# circuit.net
KiCad netlist of a schematic drawn in EAGLE
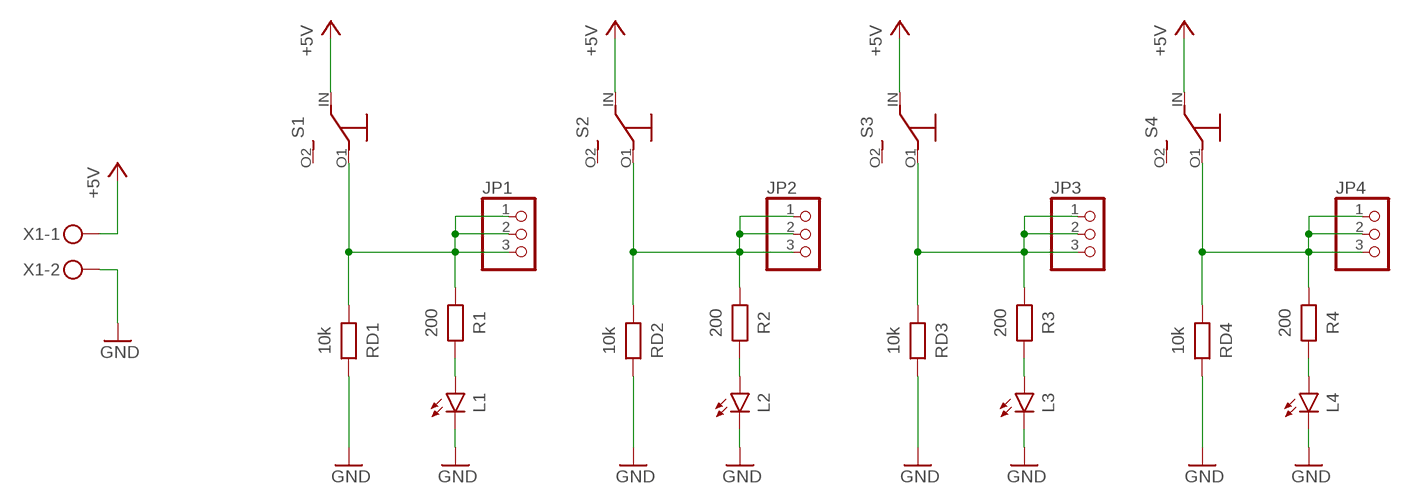
[diagram p0: schematic, sheet 1]

(export (version "E")
  (design (tool "Eeschema 10.0.6"))
  (components
    (comp (ref "JP1")
      (value "PINHD-1X3")
      (footprint "eagle-import:1X03")
      (libsource (lib "eagle-import") (part "PINHD-1X3"))
    )
    (comp (ref "JP2")
      (value "PINHD-1X3")
      (footprint "eagle-import:1X03")
      (libsource (lib "eagle-import") (part "PINHD-1X3"))
    )
    (comp (ref "JP3")
      (value "PINHD-1X3")
      (footprint "eagle-import:1X03")
      (libsource (lib "eagle-import") (part "PINHD-1X3"))
    )
    (comp (ref "JP4")
      (value "PINHD-1X3")
      (footprint "eagle-import:1X03")
      (libsource (lib "eagle-import") (part "PINHD-1X3"))
    )
    (comp (ref "L1")
      (value "LED-3MM")
      (footprint "eagle-import:LED_3MM")
      (libsource (lib "eagle-import") (part "LED-3MM"))
    )
    (comp (ref "L2")
      (value "LED-3MM")
      (footprint "eagle-import:LED_3MM")
      (libsource (lib "eagle-import") (part "LED-3MM"))
    )
    (comp (ref "L3")
      (value "LED-3MM")
      (footprint "eagle-import:LED_3MM")
      (libsource (lib "eagle-import") (part "LED-3MM"))
    )
    (comp (ref "L4")
      (value "LED-3MM")
      (footprint "eagle-import:LED_3MM")
      (libsource (lib "eagle-import") (part "LED-3MM"))
    )
    (comp (ref "R1")
      (value "200")
      (footprint "eagle-import:R_THT_4")
      (libsource (lib "eagle-import") (part "RESISTOR-10MM"))
    )
    (comp (ref "R2")
      (value "200")
      (footprint "eagle-import:R_THT_4")
      (libsource (lib "eagle-import") (part "RESISTOR-10MM"))
    )
    (comp (ref "R3")
      (value "200")
      (footprint "eagle-import:R_THT_4")
      (libsource (lib "eagle-import") (part "RESISTOR-10MM"))
    )
    (comp (ref "R4")
      (value "200")
      (footprint "eagle-import:R_THT_4")
      (libsource (lib "eagle-import") (part "RESISTOR-10MM"))
    )
    (comp (ref "RD1")
      (value "10k")
      (footprint "eagle-import:R_THT_4")
      (libsource (lib "eagle-import") (part "RESISTOR-10MM"))
    )
    (comp (ref "RD2")
      (value "10k")
      (footprint "eagle-import:R_THT_4")
      (libsource (lib "eagle-import") (part "RESISTOR-10MM"))
    )
    (comp (ref "RD3")
      (value "10k")
      (footprint "eagle-import:R_THT_4")
      (libsource (lib "eagle-import") (part "RESISTOR-10MM"))
    )
    (comp (ref "RD4")
      (value "10k")
      (footprint "eagle-import:R_THT_4")
      (libsource (lib "eagle-import") (part "RESISTOR-10MM"))
    )
    (comp (ref "S1")
      (value "SCHALTER_UM-KIPP")
      (footprint "eagle-import:SCHALTER_KIPP_UM")
      (libsource (lib "eagle-import") (part "SCHALTER_UM-KIPP"))
    )
    (comp (ref "S2")
      (value "SCHALTER_UM-KIPP")
      (footprint "eagle-import:SCHALTER_KIPP_UM")
      (libsource (lib "eagle-import") (part "SCHALTER_UM-KIPP"))
    )
    (comp (ref "S3")
      (value "SCHALTER_UM-KIPP")
      (footprint "eagle-import:SCHALTER_KIPP_UM")
      (libsource (lib "eagle-import") (part "SCHALTER_UM-KIPP"))
    )
    (comp (ref "S4")
      (value "SCHALTER_UM-KIPP")
      (footprint "eagle-import:SCHALTER_KIPP_UM")
      (libsource (lib "eagle-import") (part "SCHALTER_UM-KIPP"))
    )
    (comp (ref "X1")
      (value "STECKER_SPG_2")
      (footprint "eagle-import:STECKER_SPG_2")
      (libsource (lib "eagle-import") (part "STECKER_SPG_2"))
    )
  )
  (nets
    (net (code "1") (name "+5V") (class "Default")
      (node (ref "S1") (pin "IN") (pinfunction "IN_IN") (pintype "passive"))
      (node (ref "S2") (pin "IN") (pinfunction "IN_IN") (pintype "passive"))
      (node (ref "S3") (pin "IN") (pinfunction "IN_IN") (pintype "passive"))
      (node (ref "S4") (pin "IN") (pinfunction "IN_IN") (pintype "passive"))
      (node (ref "X1") (pin "1") (pinfunction "KL_1") (pintype "passive"))
    )
    (net (code "2") (name "GND") (class "Default")
      (node (ref "L1") (pin "K") (pinfunction "C_K") (pintype "passive"))
      (node (ref "L2") (pin "K") (pinfunction "C_K") (pintype "passive"))
      (node (ref "L3") (pin "K") (pinfunction "C_K") (pintype "passive"))
      (node (ref "L4") (pin "K") (pinfunction "C_K") (pintype "passive"))
      (node (ref "RD1") (pin "1") (pinfunction "P1_1") (pintype "passive"))
      (node (ref "RD2") (pin "1") (pinfunction "P1_1") (pintype "passive"))
      (node (ref "RD3") (pin "1") (pinfunction "P1_1") (pintype "passive"))
      (node (ref "RD4") (pin "1") (pinfunction "P1_1") (pintype "passive"))
      (node (ref "X1") (pin "2") (pinfunction "KL_2") (pintype "passive"))
    )
    (net (code "3") (name "Net-(R1-P1)") (class "Default")
      (node (ref "L1") (pin "A") (pinfunction "A_A") (pintype "passive"))
      (node (ref "R1") (pin "1") (pinfunction "P1_1") (pintype "passive"))
    )
    (net (code "4") (name "Net-(R1-P2)") (class "Default")
      (node (ref "JP1") (pin "1") (pinfunction "1_1") (pintype "passive"))
      (node (ref "JP1") (pin "2") (pinfunction "2_2") (pintype "passive"))
      (node (ref "JP1") (pin "3") (pinfunction "3_3") (pintype "passive"))
      (node (ref "R1") (pin "2") (pinfunction "P2_2") (pintype "passive"))
      (node (ref "RD1") (pin "2") (pinfunction "P2_2") (pintype "passive"))
      (node (ref "S1") (pin "O1") (pinfunction "O1_O1") (pintype "passive"))
    )
    (net (code "5") (name "Net-(R2-P1)") (class "Default")
      (node (ref "L2") (pin "A") (pinfunction "A_A") (pintype "passive"))
      (node (ref "R2") (pin "1") (pinfunction "P1_1") (pintype "passive"))
    )
    (net (code "6") (name "Net-(R2-P2)") (class "Default")
      (node (ref "JP2") (pin "1") (pinfunction "1_1") (pintype "passive"))
      (node (ref "JP2") (pin "2") (pinfunction "2_2") (pintype "passive"))
      (node (ref "JP2") (pin "3") (pinfunction "3_3") (pintype "passive"))
      (node (ref "R2") (pin "2") (pinfunction "P2_2") (pintype "passive"))
      (node (ref "RD2") (pin "2") (pinfunction "P2_2") (pintype "passive"))
      (node (ref "S2") (pin "O1") (pinfunction "O1_O1") (pintype "passive"))
    )
    (net (code "7") (name "Net-(R3-P1)") (class "Default")
      (node (ref "L3") (pin "A") (pinfunction "A_A") (pintype "passive"))
      (node (ref "R3") (pin "1") (pinfunction "P1_1") (pintype "passive"))
    )
    (net (code "8") (name "Net-(R3-P2)") (class "Default")
      (node (ref "JP3") (pin "1") (pinfunction "1_1") (pintype "passive"))
      (node (ref "JP3") (pin "2") (pinfunction "2_2") (pintype "passive"))
      (node (ref "JP3") (pin "3") (pinfunction "3_3") (pintype "passive"))
      (node (ref "R3") (pin "2") (pinfunction "P2_2") (pintype "passive"))
      (node (ref "RD3") (pin "2") (pinfunction "P2_2") (pintype "passive"))
      (node (ref "S3") (pin "O1") (pinfunction "O1_O1") (pintype "passive"))
    )
    (net (code "9") (name "Net-(R4-P1)") (class "Default")
      (node (ref "L4") (pin "A") (pinfunction "A_A") (pintype "passive"))
      (node (ref "R4") (pin "1") (pinfunction "P1_1") (pintype "passive"))
    )
    (net (code "10") (name "Net-(R4-P2)") (class "Default")
      (node (ref "JP4") (pin "1") (pinfunction "1_1") (pintype "passive"))
      (node (ref "JP4") (pin "2") (pinfunction "2_2") (pintype "passive"))
      (node (ref "JP4") (pin "3") (pinfunction "3_3") (pintype "passive"))
      (node (ref "R4") (pin "2") (pinfunction "P2_2") (pintype "passive"))
      (node (ref "RD4") (pin "2") (pinfunction "P2_2") (pintype "passive"))
      (node (ref "S4") (pin "O1") (pinfunction "O1_O1") (pintype "passive"))
    )
    (net (code "11") (name "unconnected-(S1-PadO2)") (class "Default")
      (node (ref "S1") (pin "O2") (pinfunction "O2_O2") (pintype "passive"))
    )
    (net (code "12") (name "unconnected-(S2-PadO2)") (class "Default")
      (node (ref "S2") (pin "O2") (pinfunction "O2_O2") (pintype "passive"))
    )
    (net (code "13") (name "unconnected-(S3-PadO2)") (class "Default")
      (node (ref "S3") (pin "O2") (pinfunction "O2_O2") (pintype "passive"))
    )
    (net (code "14") (name "unconnected-(S4-PadO2)") (class "Default")
      (node (ref "S4") (pin "O2") (pinfunction "O2_O2") (pintype "passive"))
    )
  )
)
